# MCU.net
KiCad netlist of a schematic drawn in Altium Designer
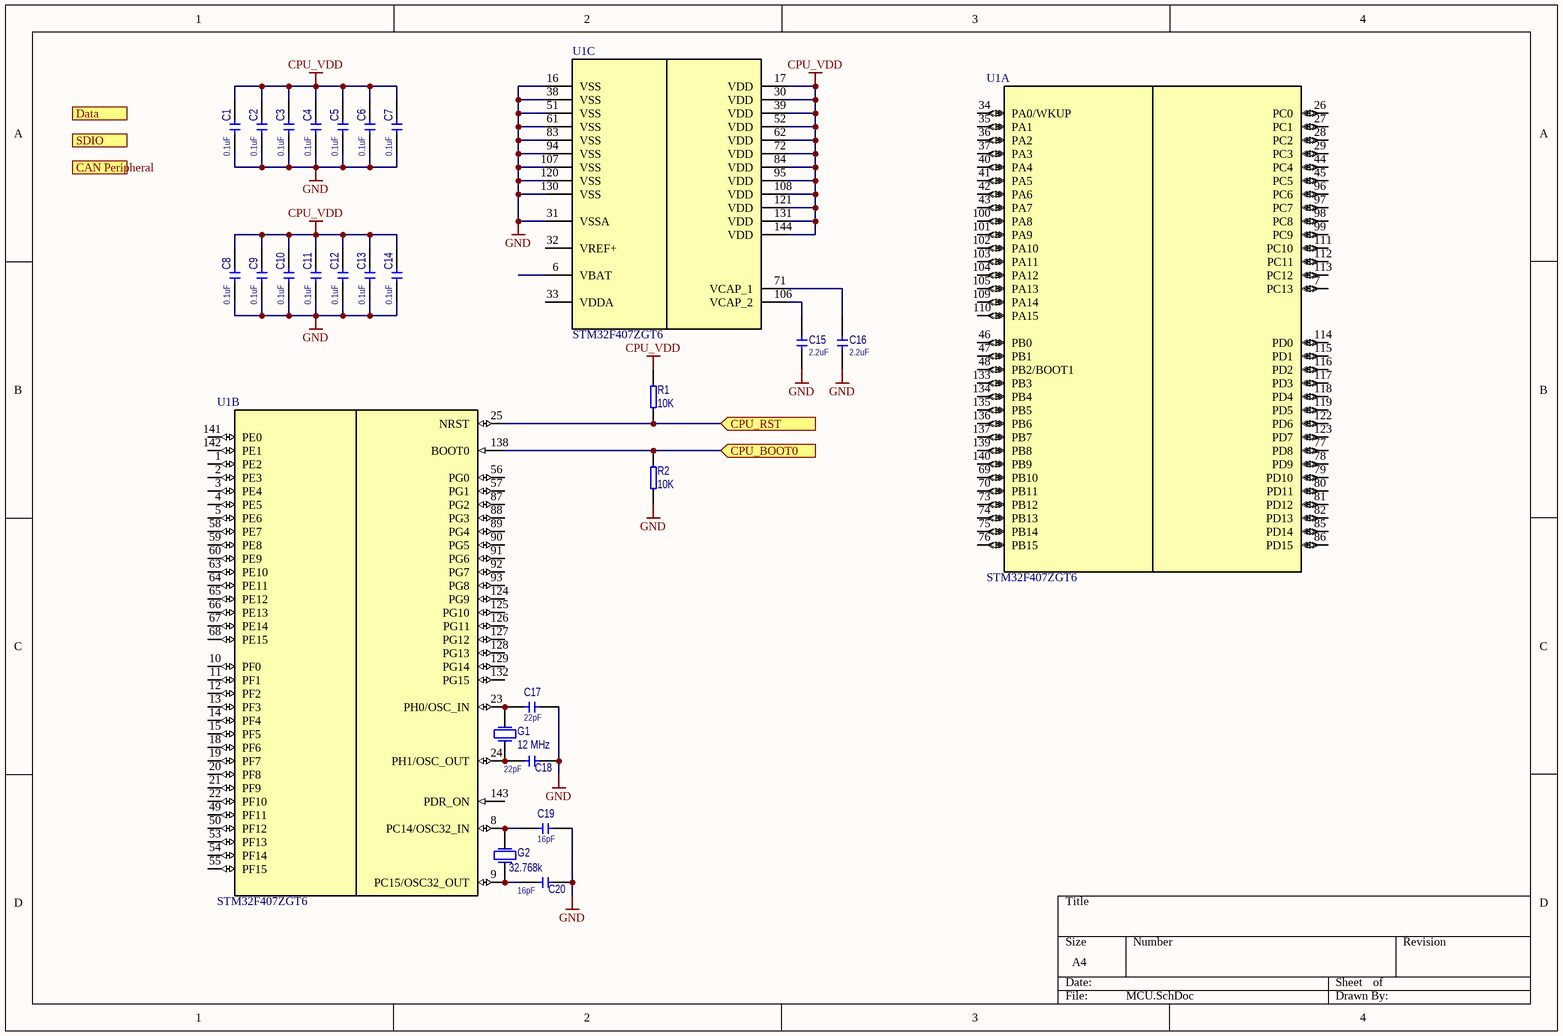
[diagram p0: MCU.SchDoc]

(export (version "E")
  (design (tool "Eeschema 10.0.6"))
  (components
    (comp (ref "C1")
      (value "0.1uF")
      (footprint "CERCAP 0603")
      (description "Capacitor")
      (fields (field (name "Comment") "CERCAP 0603 0.1uF * X7R"))
      (libsource (lib "!main") (part "!Capacitor"))
    )
    (comp (ref "C2")
      (value "0.1uF")
      (footprint "CERCAP 0603")
      (description "Capacitor")
      (fields (field (name "Comment") "CERCAP 0603 0.1uF * X7R"))
      (libsource (lib "!main") (part "!Capacitor"))
    )
    (comp (ref "C3")
      (value "0.1uF")
      (footprint "CERCAP 0603")
      (description "Capacitor")
      (fields (field (name "Comment") "CERCAP 0603 0.1uF * X7R"))
      (libsource (lib "!main") (part "!Capacitor"))
    )
    (comp (ref "C4")
      (value "0.1uF")
      (footprint "CERCAP 0603")
      (description "Capacitor")
      (fields (field (name "Comment") "CERCAP 0603 0.1uF * X7R"))
      (libsource (lib "!main") (part "!Capacitor"))
    )
    (comp (ref "C5")
      (value "0.1uF")
      (footprint "CERCAP 0603")
      (description "Capacitor")
      (fields (field (name "Comment") "CERCAP 0603 0.1uF * X7R"))
      (libsource (lib "!main") (part "!Capacitor"))
    )
    (comp (ref "C6")
      (value "0.1uF")
      (footprint "CERCAP 0603")
      (description "Capacitor")
      (fields (field (name "Comment") "CERCAP 0603 0.1uF * X7R"))
      (libsource (lib "!main") (part "!Capacitor"))
    )
    (comp (ref "C7")
      (value "0.1uF")
      (footprint "CERCAP 0603")
      (description "Capacitor")
      (fields (field (name "Comment") "CERCAP 0603 0.1uF * X7R"))
      (libsource (lib "!main") (part "!Capacitor"))
    )
    (comp (ref "C8")
      (value "0.1uF")
      (footprint "CERCAP 0603")
      (description "Capacitor")
      (fields (field (name "Comment") "CERCAP 0603 0.1uF * X7R"))
      (libsource (lib "!main") (part "!Capacitor"))
    )
    (comp (ref "C9")
      (value "0.1uF")
      (footprint "CERCAP 0603")
      (description "Capacitor")
      (fields (field (name "Comment") "CERCAP 0603 0.1uF * X7R"))
      (libsource (lib "!main") (part "!Capacitor"))
    )
    (comp (ref "C10")
      (value "0.1uF")
      (footprint "CERCAP 0603")
      (description "Capacitor")
      (fields (field (name "Comment") "CERCAP 0603 0.1uF * X7R"))
      (libsource (lib "!main") (part "!Capacitor"))
    )
    (comp (ref "C11")
      (value "0.1uF")
      (footprint "CERCAP 0603")
      (description "Capacitor")
      (fields (field (name "Comment") "CERCAP 0603 0.1uF * X7R"))
      (libsource (lib "!main") (part "!Capacitor"))
    )
    (comp (ref "C12")
      (value "0.1uF")
      (footprint "CERCAP 0603")
      (description "Capacitor")
      (fields (field (name "Comment") "CERCAP 0603 0.1uF * X7R"))
      (libsource (lib "!main") (part "!Capacitor"))
    )
    (comp (ref "C13")
      (value "0.1uF")
      (footprint "CERCAP 0603")
      (description "Capacitor")
      (fields (field (name "Comment") "CERCAP 0603 0.1uF * X7R"))
      (libsource (lib "!main") (part "!Capacitor"))
    )
    (comp (ref "C14")
      (value "0.1uF")
      (footprint "CERCAP 0603")
      (description "Capacitor")
      (fields (field (name "Comment") "CERCAP 0603 0.1uF * X7R"))
      (libsource (lib "!main") (part "!Capacitor"))
    )
    (comp (ref "C15")
      (value "2.2uF")
      (footprint "CERCAP 0603")
      (description "Capacitor")
      (fields (field (name "Comment") "CERCAP 0603 2.2uF * X7R"))
      (libsource (lib "!main") (part "!Capacitor"))
    )
    (comp (ref "C16")
      (value "2.2uF")
      (footprint "CERCAP 0603")
      (description "Capacitor")
      (fields (field (name "Comment") "CERCAP 0603 2.2uF * X7R"))
      (libsource (lib "!main") (part "!Capacitor"))
    )
    (comp (ref "C17")
      (value "22pF")
      (footprint "CERCAP 0402")
      (description "Capacitor")
      (fields (field (name "Comment") "CERCAP 0402 22pF * X7R"))
      (libsource (lib "!main") (part "!Capacitor"))
    )
    (comp (ref "C18")
      (value "22pF")
      (footprint "CERCAP 0402")
      (description "Capacitor")
      (fields (field (name "Comment") "CERCAP 0402 22pF * X7R"))
      (libsource (lib "!main") (part "!Capacitor"))
    )
    (comp (ref "C19")
      (value "16pF")
      (footprint "CERCAP 0402")
      (description "Capacitor")
      (fields (field (name "Comment") "CERCAP 0402 16pF * X7R"))
      (libsource (lib "!main") (part "!Capacitor"))
    )
    (comp (ref "C20")
      (value "16pF")
      (footprint "CERCAP 0402")
      (description "Capacitor")
      (fields (field (name "Comment") "CERCAP 0402 16pF * X7R"))
      (libsource (lib "!main") (part "!Capacitor"))
    )
    (comp (ref "G1")
      (value "12 MHz")
      (footprint "3225")
      (description "Crystal")
      (fields (field (name "Comment") "322512 MHz"))
      (libsource (lib "!main") (part "Crystal"))
    )
    (comp (ref "G2")
      (value "32.768k")
      (footprint "1210")
      (description "Crystal")
      (fields (field (name "Comment") "121032.768k"))
      (libsource (lib "!main") (part "Crystal"))
    )
    (comp (ref "R1")
      (value "10K")
      (footprint "RES 0402")
      (description "Resistor")
      (fields (field (name "Comment") "RES 0402 10K"))
      (libsource (lib "!main") (part "!Resistor"))
    )
    (comp (ref "R2")
      (value "10K")
      (footprint "RES 0402")
      (description "Resistor")
      (fields (field (name "Comment") "RES 0402 10K"))
      (libsource (lib "!main") (part "!Resistor"))
    )
    (comp (ref "U1")
      (value "STM32F407ZGT6")
      (footprint "LQFP-144")
      (description "Coretx-M4")
      (libsource (lib "MCU_CPU") (part "STM32F407ZGT6"))
    )
  )
  (nets
    (net (code "2") (name "/CPU_BOOT0") (class "Default")
      (node (ref "R2") (pin "2") (pinfunction "12_2") (pintype "passive"))
      (node (ref "U1") (pin "138") (pinfunction "BOOT0_138") (pintype "input"))
    )
    (net (code "3") (name "/CPU_RST") (class "Default")
      (node (ref "R1") (pin "2") (pinfunction "12_2") (pintype "passive"))
      (node (ref "U1") (pin "25") (pinfunction "NRST_25") (pintype "bidirectional"))
    )
    (net (code "6") (name "CPU_VDD") (class "Default")
      (node (ref "C1") (pin "1") (pintype "passive"))
      (node (ref "C10") (pin "1") (pintype "passive"))
      (node (ref "C11") (pin "1") (pintype "passive"))
      (node (ref "C12") (pin "1") (pintype "passive"))
      (node (ref "C13") (pin "1") (pintype "passive"))
      (node (ref "C14") (pin "1") (pintype "passive"))
      (node (ref "C2") (pin "1") (pintype "passive"))
      (node (ref "C3") (pin "1") (pintype "passive"))
      (node (ref "C4") (pin "1") (pintype "passive"))
      (node (ref "C5") (pin "1") (pintype "passive"))
      (node (ref "C6") (pin "1") (pintype "passive"))
      (node (ref "C7") (pin "1") (pintype "passive"))
      (node (ref "C8") (pin "1") (pintype "passive"))
      (node (ref "C9") (pin "1") (pintype "passive"))
      (node (ref "R1") (pin "1") (pinfunction "11_1") (pintype "passive"))
      (node (ref "U1") (pin "108") (pinfunction "VDD_108") (pintype "power_in"))
      (node (ref "U1") (pin "121") (pinfunction "VDD_121") (pintype "power_in"))
      (node (ref "U1") (pin "131") (pinfunction "VDD_131") (pintype "power_in"))
      (node (ref "U1") (pin "144") (pinfunction "VDD_144") (pintype "power_in"))
      (node (ref "U1") (pin "17") (pinfunction "VDD_17") (pintype "power_in"))
      (node (ref "U1") (pin "30") (pinfunction "VDD_30") (pintype "power_in"))
      (node (ref "U1") (pin "39") (pinfunction "VDD_39") (pintype "power_in"))
      (node (ref "U1") (pin "52") (pinfunction "VDD_52") (pintype "power_in"))
      (node (ref "U1") (pin "62") (pinfunction "VDD_62") (pintype "power_in"))
      (node (ref "U1") (pin "72") (pinfunction "VDD_72") (pintype "power_in"))
      (node (ref "U1") (pin "84") (pinfunction "VDD_84") (pintype "power_in"))
      (node (ref "U1") (pin "95") (pinfunction "VDD_95") (pintype "power_in"))
    )
    (net (code "7") (name "GND") (class "Default")
      (node (ref "C1") (pin "2") (pintype "passive"))
      (node (ref "C10") (pin "2") (pintype "passive"))
      (node (ref "C11") (pin "2") (pintype "passive"))
      (node (ref "C12") (pin "2") (pintype "passive"))
      (node (ref "C13") (pin "2") (pintype "passive"))
      (node (ref "C14") (pin "2") (pintype "passive"))
      (node (ref "C15") (pin "2") (pintype "passive"))
      (node (ref "C16") (pin "2") (pintype "passive"))
      (node (ref "C17") (pin "2") (pintype "passive"))
      (node (ref "C18") (pin "2") (pintype "passive"))
      (node (ref "C19") (pin "2") (pintype "passive"))
      (node (ref "C2") (pin "2") (pintype "passive"))
      (node (ref "C20") (pin "2") (pintype "passive"))
      (node (ref "C3") (pin "2") (pintype "passive"))
      (node (ref "C4") (pin "2") (pintype "passive"))
      (node (ref "C5") (pin "2") (pintype "passive"))
      (node (ref "C6") (pin "2") (pintype "passive"))
      (node (ref "C7") (pin "2") (pintype "passive"))
      (node (ref "C8") (pin "2") (pintype "passive"))
      (node (ref "C9") (pin "2") (pintype "passive"))
      (node (ref "R2") (pin "1") (pinfunction "11_1") (pintype "passive"))
      (node (ref "U1") (pin "107") (pinfunction "VSS_107") (pintype "power_in"))
      (node (ref "U1") (pin "120") (pinfunction "VSS_120") (pintype "power_in"))
      (node (ref "U1") (pin "130") (pinfunction "VSS_130") (pintype "power_in"))
      (node (ref "U1") (pin "16") (pinfunction "VSS_16") (pintype "power_in"))
      (node (ref "U1") (pin "31") (pinfunction "VSSA_31") (pintype "power_in"))
      (node (ref "U1") (pin "38") (pinfunction "VSS_38") (pintype "power_in"))
      (node (ref "U1") (pin "51") (pinfunction "VSS_51") (pintype "power_in"))
      (node (ref "U1") (pin "61") (pinfunction "VSS_61") (pintype "power_in"))
      (node (ref "U1") (pin "83") (pinfunction "VSS_83") (pintype "power_in"))
      (node (ref "U1") (pin "94") (pinfunction "VSS_94") (pintype "power_in"))
    )
    (net (code "8") (name "Net-(U1B-PC14{slash}OSC32_IN)") (class "Default")
      (node (ref "C19") (pin "1") (pintype "passive"))
      (node (ref "G2") (pin "1") (pintype "passive"))
      (node (ref "U1") (pin "8") (pinfunction "PC14/OSC32_IN_8") (pintype "bidirectional"))
    )
    (net (code "9") (name "Net-(U1B-PC15{slash}OSC32_OUT)") (class "Default")
      (node (ref "C20") (pin "1") (pintype "passive"))
      (node (ref "G2") (pin "2") (pintype "passive"))
      (node (ref "U1") (pin "9") (pinfunction "PC15/OSC32_OUT_9") (pintype "bidirectional"))
    )
    (net (code "10") (name "Net-(U1B-PH0{slash}OSC_IN)") (class "Default")
      (node (ref "C17") (pin "1") (pintype "passive"))
      (node (ref "G1") (pin "1") (pintype "passive"))
      (node (ref "U1") (pin "23") (pinfunction "PH0/OSC_IN_23") (pintype "bidirectional"))
    )
    (net (code "11") (name "Net-(U1B-PH1{slash}OSC_OUT)") (class "Default")
      (node (ref "C18") (pin "1") (pintype "passive"))
      (node (ref "G1") (pin "2") (pintype "passive"))
      (node (ref "U1") (pin "24") (pinfunction "PH1/OSC_OUT_24") (pintype "bidirectional"))
    )
    (net (code "12") (name "Net-(U1C-VCAP_1)") (class "Default")
      (node (ref "C16") (pin "1") (pintype "passive"))
      (node (ref "U1") (pin "71") (pinfunction "VCAP_1_71") (pintype "power_in"))
    )
    (net (code "13") (name "Net-(U1C-VCAP_2)") (class "Default")
      (node (ref "C15") (pin "1") (pintype "passive"))
      (node (ref "U1") (pin "106") (pinfunction "VCAP_2_106") (pintype "power_in"))
    )
    (net (code "14") (name "unconnected-(U1A-PA0{slash}WKUP-Pad34)") (class "Default")
      (node (ref "U1") (pin "34") (pinfunction "PA0/WKUP_34") (pintype "bidirectional"))
    )
    (net (code "15") (name "unconnected-(U1A-PA1-Pad35)") (class "Default")
      (node (ref "U1") (pin "35") (pinfunction "PA1_35") (pintype "bidirectional"))
    )
    (net (code "16") (name "unconnected-(U1A-PA2-Pad36)") (class "Default")
      (node (ref "U1") (pin "36") (pinfunction "PA2_36") (pintype "bidirectional"))
    )
    (net (code "17") (name "unconnected-(U1A-PA3-Pad37)") (class "Default")
      (node (ref "U1") (pin "37") (pinfunction "PA3_37") (pintype "bidirectional"))
    )
    (net (code "18") (name "unconnected-(U1A-PA4-Pad40)") (class "Default")
      (node (ref "U1") (pin "40") (pinfunction "PA4_40") (pintype "bidirectional"))
    )
    (net (code "19") (name "unconnected-(U1A-PA5-Pad41)") (class "Default")
      (node (ref "U1") (pin "41") (pinfunction "PA5_41") (pintype "bidirectional"))
    )
    (net (code "20") (name "unconnected-(U1A-PA6-Pad42)") (class "Default")
      (node (ref "U1") (pin "42") (pinfunction "PA6_42") (pintype "bidirectional"))
    )
    (net (code "21") (name "unconnected-(U1A-PA7-Pad43)") (class "Default")
      (node (ref "U1") (pin "43") (pinfunction "PA7_43") (pintype "bidirectional"))
    )
    (net (code "22") (name "unconnected-(U1A-PA8-Pad100)") (class "Default")
      (node (ref "U1") (pin "100") (pinfunction "PA8_100") (pintype "bidirectional"))
    )
    (net (code "23") (name "unconnected-(U1A-PA9-Pad101)") (class "Default")
      (node (ref "U1") (pin "101") (pinfunction "PA9_101") (pintype "bidirectional"))
    )
    (net (code "24") (name "unconnected-(U1A-PA10-Pad102)") (class "Default")
      (node (ref "U1") (pin "102") (pinfunction "PA10_102") (pintype "bidirectional"))
    )
    (net (code "25") (name "unconnected-(U1A-PA11-Pad103)") (class "Default")
      (node (ref "U1") (pin "103") (pinfunction "PA11_103") (pintype "bidirectional"))
    )
    (net (code "26") (name "unconnected-(U1A-PA12-Pad104)") (class "Default")
      (node (ref "U1") (pin "104") (pinfunction "PA12_104") (pintype "bidirectional"))
    )
    (net (code "27") (name "unconnected-(U1A-PA13-Pad105)") (class "Default")
      (node (ref "U1") (pin "105") (pinfunction "PA13_105") (pintype "bidirectional"))
    )
    (net (code "28") (name "unconnected-(U1A-PA14-Pad109)") (class "Default")
      (node (ref "U1") (pin "109") (pinfunction "PA14_109") (pintype "bidirectional"))
    )
    (net (code "29") (name "unconnected-(U1A-PA15-Pad110)") (class "Default")
      (node (ref "U1") (pin "110") (pinfunction "PA15_110") (pintype "bidirectional"))
    )
    (net (code "30") (name "unconnected-(U1A-PB0-Pad46)") (class "Default")
      (node (ref "U1") (pin "46") (pinfunction "PB0_46") (pintype "bidirectional"))
    )
    (net (code "31") (name "unconnected-(U1A-PB1-Pad47)") (class "Default")
      (node (ref "U1") (pin "47") (pinfunction "PB1_47") (pintype "bidirectional"))
    )
    (net (code "32") (name "unconnected-(U1A-PB2{slash}BOOT1-Pad48)") (class "Default")
      (node (ref "U1") (pin "48") (pinfunction "PB2/BOOT1_48") (pintype "bidirectional"))
    )
    (net (code "33") (name "unconnected-(U1A-PB3-Pad133)") (class "Default")
      (node (ref "U1") (pin "133") (pinfunction "PB3_133") (pintype "bidirectional"))
    )
    (net (code "34") (name "unconnected-(U1A-PB4-Pad134)") (class "Default")
      (node (ref "U1") (pin "134") (pinfunction "PB4_134") (pintype "bidirectional"))
    )
    (net (code "35") (name "unconnected-(U1A-PB5-Pad135)") (class "Default")
      (node (ref "U1") (pin "135") (pinfunction "PB5_135") (pintype "bidirectional"))
    )
    (net (code "36") (name "unconnected-(U1A-PB6-Pad136)") (class "Default")
      (node (ref "U1") (pin "136") (pinfunction "PB6_136") (pintype "bidirectional"))
    )
    (net (code "37") (name "unconnected-(U1A-PB7-Pad137)") (class "Default")
      (node (ref "U1") (pin "137") (pinfunction "PB7_137") (pintype "bidirectional"))
    )
    (net (code "38") (name "unconnected-(U1A-PB8-Pad139)") (class "Default")
      (node (ref "U1") (pin "139") (pinfunction "PB8_139") (pintype "bidirectional"))
    )
    (net (code "39") (name "unconnected-(U1A-PB9-Pad140)") (class "Default")
      (node (ref "U1") (pin "140") (pinfunction "PB9_140") (pintype "bidirectional"))
    )
    (net (code "40") (name "unconnected-(U1A-PB10-Pad69)") (class "Default")
      (node (ref "U1") (pin "69") (pinfunction "PB10_69") (pintype "bidirectional"))
    )
    (net (code "41") (name "unconnected-(U1A-PB11-Pad70)") (class "Default")
      (node (ref "U1") (pin "70") (pinfunction "PB11_70") (pintype "bidirectional"))
    )
    (net (code "42") (name "unconnected-(U1A-PB12-Pad73)") (class "Default")
      (node (ref "U1") (pin "73") (pinfunction "PB12_73") (pintype "bidirectional"))
    )
    (net (code "43") (name "unconnected-(U1A-PB13-Pad74)") (class "Default")
      (node (ref "U1") (pin "74") (pinfunction "PB13_74") (pintype "bidirectional"))
    )
    (net (code "44") (name "unconnected-(U1A-PB14-Pad75)") (class "Default")
      (node (ref "U1") (pin "75") (pinfunction "PB14_75") (pintype "bidirectional"))
    )
    (net (code "45") (name "unconnected-(U1A-PB15-Pad76)") (class "Default")
      (node (ref "U1") (pin "76") (pinfunction "PB15_76") (pintype "bidirectional"))
    )
    (net (code "46") (name "unconnected-(U1A-PC0-Pad26)") (class "Default")
      (node (ref "U1") (pin "26") (pinfunction "PC0_26") (pintype "bidirectional"))
    )
    (net (code "47") (name "unconnected-(U1A-PC1-Pad27)") (class "Default")
      (node (ref "U1") (pin "27") (pinfunction "PC1_27") (pintype "bidirectional"))
    )
    (net (code "48") (name "unconnected-(U1A-PC2-Pad28)") (class "Default")
      (node (ref "U1") (pin "28") (pinfunction "PC2_28") (pintype "bidirectional"))
    )
    (net (code "49") (name "unconnected-(U1A-PC3-Pad29)") (class "Default")
      (node (ref "U1") (pin "29") (pinfunction "PC3_29") (pintype "bidirectional"))
    )
    (net (code "50") (name "unconnected-(U1A-PC4-Pad44)") (class "Default")
      (node (ref "U1") (pin "44") (pinfunction "PC4_44") (pintype "bidirectional"))
    )
    (net (code "51") (name "unconnected-(U1A-PC5-Pad45)") (class "Default")
      (node (ref "U1") (pin "45") (pinfunction "PC5_45") (pintype "bidirectional"))
    )
    (net (code "52") (name "unconnected-(U1A-PC6-Pad96)") (class "Default")
      (node (ref "U1") (pin "96") (pinfunction "PC6_96") (pintype "bidirectional"))
    )
    (net (code "53") (name "unconnected-(U1A-PC7-Pad97)") (class "Default")
      (node (ref "U1") (pin "97") (pinfunction "PC7_97") (pintype "bidirectional"))
    )
    (net (code "54") (name "unconnected-(U1A-PC8-Pad98)") (class "Default")
      (node (ref "U1") (pin "98") (pinfunction "PC8_98") (pintype "bidirectional"))
    )
    (net (code "55") (name "unconnected-(U1A-PC9-Pad99)") (class "Default")
      (node (ref "U1") (pin "99") (pinfunction "PC9_99") (pintype "bidirectional"))
    )
    (net (code "56") (name "unconnected-(U1A-PC10-Pad111)") (class "Default")
      (node (ref "U1") (pin "111") (pinfunction "PC10_111") (pintype "bidirectional"))
    )
    (net (code "57") (name "unconnected-(U1A-PC11-Pad112)") (class "Default")
      (node (ref "U1") (pin "112") (pinfunction "PC11_112") (pintype "bidirectional"))
    )
    (net (code "58") (name "unconnected-(U1A-PC12-Pad113)") (class "Default")
      (node (ref "U1") (pin "113") (pinfunction "PC12_113") (pintype "bidirectional"))
    )
    (net (code "59") (name "unconnected-(U1A-PC13-Pad7)") (class "Default")
      (node (ref "U1") (pin "7") (pinfunction "PC13_7") (pintype "bidirectional"))
    )
    (net (code "60") (name "unconnected-(U1A-PD0-Pad114)") (class "Default")
      (node (ref "U1") (pin "114") (pinfunction "PD0_114") (pintype "bidirectional"))
    )
    (net (code "61") (name "unconnected-(U1A-PD1-Pad115)") (class "Default")
      (node (ref "U1") (pin "115") (pinfunction "PD1_115") (pintype "bidirectional"))
    )
    (net (code "62") (name "unconnected-(U1A-PD2-Pad116)") (class "Default")
      (node (ref "U1") (pin "116") (pinfunction "PD2_116") (pintype "bidirectional"))
    )
    (net (code "63") (name "unconnected-(U1A-PD3-Pad117)") (class "Default")
      (node (ref "U1") (pin "117") (pinfunction "PD3_117") (pintype "bidirectional"))
    )
    (net (code "64") (name "unconnected-(U1A-PD4-Pad118)") (class "Default")
      (node (ref "U1") (pin "118") (pinfunction "PD4_118") (pintype "bidirectional"))
    )
    (net (code "65") (name "unconnected-(U1A-PD5-Pad119)") (class "Default")
      (node (ref "U1") (pin "119") (pinfunction "PD5_119") (pintype "bidirectional"))
    )
    (net (code "66") (name "unconnected-(U1A-PD6-Pad122)") (class "Default")
      (node (ref "U1") (pin "122") (pinfunction "PD6_122") (pintype "bidirectional"))
    )
    (net (code "67") (name "unconnected-(U1A-PD7-Pad123)") (class "Default")
      (node (ref "U1") (pin "123") (pinfunction "PD7_123") (pintype "bidirectional"))
    )
    (net (code "68") (name "unconnected-(U1A-PD8-Pad77)") (class "Default")
      (node (ref "U1") (pin "77") (pinfunction "PD8_77") (pintype "bidirectional"))
    )
    (net (code "69") (name "unconnected-(U1A-PD9-Pad78)") (class "Default")
      (node (ref "U1") (pin "78") (pinfunction "PD9_78") (pintype "bidirectional"))
    )
    (net (code "70") (name "unconnected-(U1A-PD10-Pad79)") (class "Default")
      (node (ref "U1") (pin "79") (pinfunction "PD10_79") (pintype "bidirectional"))
    )
    (net (code "71") (name "unconnected-(U1A-PD11-Pad80)") (class "Default")
      (node (ref "U1") (pin "80") (pinfunction "PD11_80") (pintype "bidirectional"))
    )
    (net (code "72") (name "unconnected-(U1A-PD12-Pad81)") (class "Default")
      (node (ref "U1") (pin "81") (pinfunction "PD12_81") (pintype "bidirectional"))
    )
    (net (code "73") (name "unconnected-(U1A-PD13-Pad82)") (class "Default")
      (node (ref "U1") (pin "82") (pinfunction "PD13_82") (pintype "bidirectional"))
    )
    (net (code "74") (name "unconnected-(U1A-PD14-Pad85)") (class "Default")
      (node (ref "U1") (pin "85") (pinfunction "PD14_85") (pintype "bidirectional"))
    )
    (net (code "75") (name "unconnected-(U1A-PD15-Pad86)") (class "Default")
      (node (ref "U1") (pin "86") (pinfunction "PD15_86") (pintype "bidirectional"))
    )
    (net (code "76") (name "unconnected-(U1B-PDR_ON-Pad143)") (class "Default")
      (node (ref "U1") (pin "143") (pinfunction "PDR_ON_143") (pintype "input"))
    )
    (net (code "77") (name "unconnected-(U1B-PE0-Pad141)") (class "Default")
      (node (ref "U1") (pin "141") (pinfunction "PE0_141") (pintype "bidirectional"))
    )
    (net (code "78") (name "unconnected-(U1B-PE1-Pad142)") (class "Default")
      (node (ref "U1") (pin "142") (pinfunction "PE1_142") (pintype "bidirectional"))
    )
    (net (code "79") (name "unconnected-(U1B-PE2-Pad1)") (class "Default")
      (node (ref "U1") (pin "1") (pinfunction "PE2_1") (pintype "bidirectional"))
    )
    (net (code "80") (name "unconnected-(U1B-PE3-Pad2)") (class "Default")
      (node (ref "U1") (pin "2") (pinfunction "PE3_2") (pintype "bidirectional"))
    )
    (net (code "81") (name "unconnected-(U1B-PE4-Pad3)") (class "Default")
      (node (ref "U1") (pin "3") (pinfunction "PE4_3") (pintype "bidirectional"))
    )
    (net (code "82") (name "unconnected-(U1B-PE5-Pad4)") (class "Default")
      (node (ref "U1") (pin "4") (pinfunction "PE5_4") (pintype "bidirectional"))
    )
    (net (code "83") (name "unconnected-(U1B-PE6-Pad5)") (class "Default")
      (node (ref "U1") (pin "5") (pinfunction "PE6_5") (pintype "bidirectional"))
    )
    (net (code "84") (name "unconnected-(U1B-PE7-Pad58)") (class "Default")
      (node (ref "U1") (pin "58") (pinfunction "PE7_58") (pintype "bidirectional"))
    )
    (net (code "85") (name "unconnected-(U1B-PE8-Pad59)") (class "Default")
      (node (ref "U1") (pin "59") (pinfunction "PE8_59") (pintype "bidirectional"))
    )
    (net (code "86") (name "unconnected-(U1B-PE9-Pad60)") (class "Default")
      (node (ref "U1") (pin "60") (pinfunction "PE9_60") (pintype "bidirectional"))
    )
    (net (code "87") (name "unconnected-(U1B-PE10-Pad63)") (class "Default")
      (node (ref "U1") (pin "63") (pinfunction "PE10_63") (pintype "bidirectional"))
    )
    (net (code "88") (name "unconnected-(U1B-PE11-Pad64)") (class "Default")
      (node (ref "U1") (pin "64") (pinfunction "PE11_64") (pintype "bidirectional"))
    )
    (net (code "89") (name "unconnected-(U1B-PE12-Pad65)") (class "Default")
      (node (ref "U1") (pin "65") (pinfunction "PE12_65") (pintype "bidirectional"))
    )
    (net (code "90") (name "unconnected-(U1B-PE13-Pad66)") (class "Default")
      (node (ref "U1") (pin "66") (pinfunction "PE13_66") (pintype "bidirectional"))
    )
    (net (code "91") (name "unconnected-(U1B-PE14-Pad67)") (class "Default")
      (node (ref "U1") (pin "67") (pinfunction "PE14_67") (pintype "bidirectional"))
    )
    (net (code "92") (name "unconnected-(U1B-PE15-Pad68)") (class "Default")
      (node (ref "U1") (pin "68") (pinfunction "PE15_68") (pintype "bidirectional"))
    )
    (net (code "93") (name "unconnected-(U1B-PF0-Pad10)") (class "Default")
      (node (ref "U1") (pin "10") (pinfunction "PF0_10") (pintype "bidirectional"))
    )
    (net (code "94") (name "unconnected-(U1B-PF1-Pad11)") (class "Default")
      (node (ref "U1") (pin "11") (pinfunction "PF1_11") (pintype "bidirectional"))
    )
    (net (code "95") (name "unconnected-(U1B-PF2-Pad12)") (class "Default")
      (node (ref "U1") (pin "12") (pinfunction "PF2_12") (pintype "bidirectional"))
    )
    (net (code "96") (name "unconnected-(U1B-PF3-Pad13)") (class "Default")
      (node (ref "U1") (pin "13") (pinfunction "PF3_13") (pintype "bidirectional"))
    )
    (net (code "97") (name "unconnected-(U1B-PF4-Pad14)") (class "Default")
      (node (ref "U1") (pin "14") (pinfunction "PF4_14") (pintype "bidirectional"))
    )
    (net (code "98") (name "unconnected-(U1B-PF5-Pad15)") (class "Default")
      (node (ref "U1") (pin "15") (pinfunction "PF5_15") (pintype "bidirectional"))
    )
    (net (code "99") (name "unconnected-(U1B-PF6-Pad18)") (class "Default")
      (node (ref "U1") (pin "18") (pinfunction "PF6_18") (pintype "bidirectional"))
    )
    (net (code "100") (name "unconnected-(U1B-PF7-Pad19)") (class "Default")
      (node (ref "U1") (pin "19") (pinfunction "PF7_19") (pintype "bidirectional"))
    )
    (net (code "101") (name "unconnected-(U1B-PF8-Pad20)") (class "Default")
      (node (ref "U1") (pin "20") (pinfunction "PF8_20") (pintype "bidirectional"))
    )
    (net (code "102") (name "unconnected-(U1B-PF9-Pad21)") (class "Default")
      (node (ref "U1") (pin "21") (pinfunction "PF9_21") (pintype "bidirectional"))
    )
    (net (code "103") (name "unconnected-(U1B-PF10-Pad22)") (class "Default")
      (node (ref "U1") (pin "22") (pinfunction "PF10_22") (pintype "bidirectional"))
    )
    (net (code "104") (name "unconnected-(U1B-PF11-Pad49)") (class "Default")
      (node (ref "U1") (pin "49") (pinfunction "PF11_49") (pintype "bidirectional"))
    )
    (net (code "105") (name "unconnected-(U1B-PF12-Pad50)") (class "Default")
      (node (ref "U1") (pin "50") (pinfunction "PF12_50") (pintype "bidirectional"))
    )
    (net (code "106") (name "unconnected-(U1B-PF13-Pad53)") (class "Default")
      (node (ref "U1") (pin "53") (pinfunction "PF13_53") (pintype "bidirectional"))
    )
    (net (code "107") (name "unconnected-(U1B-PF14-Pad54)") (class "Default")
      (node (ref "U1") (pin "54") (pinfunction "PF14_54") (pintype "bidirectional"))
    )
    (net (code "108") (name "unconnected-(U1B-PF15-Pad55)") (class "Default")
      (node (ref "U1") (pin "55") (pinfunction "PF15_55") (pintype "bidirectional"))
    )
    (net (code "109") (name "unconnected-(U1B-PG0-Pad56)") (class "Default")
      (node (ref "U1") (pin "56") (pinfunction "PG0_56") (pintype "bidirectional"))
    )
    (net (code "110") (name "unconnected-(U1B-PG1-Pad57)") (class "Default")
      (node (ref "U1") (pin "57") (pinfunction "PG1_57") (pintype "bidirectional"))
    )
    (net (code "111") (name "unconnected-(U1B-PG2-Pad87)") (class "Default")
      (node (ref "U1") (pin "87") (pinfunction "PG2_87") (pintype "bidirectional"))
    )
    (net (code "112") (name "unconnected-(U1B-PG3-Pad88)") (class "Default")
      (node (ref "U1") (pin "88") (pinfunction "PG3_88") (pintype "bidirectional"))
    )
    (net (code "113") (name "unconnected-(U1B-PG4-Pad89)") (class "Default")
      (node (ref "U1") (pin "89") (pinfunction "PG4_89") (pintype "bidirectional"))
    )
    (net (code "114") (name "unconnected-(U1B-PG5-Pad90)") (class "Default")
      (node (ref "U1") (pin "90") (pinfunction "PG5_90") (pintype "bidirectional"))
    )
    (net (code "115") (name "unconnected-(U1B-PG6-Pad91)") (class "Default")
      (node (ref "U1") (pin "91") (pinfunction "PG6_91") (pintype "bidirectional"))
    )
    (net (code "116") (name "unconnected-(U1B-PG7-Pad92)") (class "Default")
      (node (ref "U1") (pin "92") (pinfunction "PG7_92") (pintype "bidirectional"))
    )
    (net (code "117") (name "unconnected-(U1B-PG8-Pad93)") (class "Default")
      (node (ref "U1") (pin "93") (pinfunction "PG8_93") (pintype "bidirectional"))
    )
    (net (code "118") (name "unconnected-(U1B-PG9-Pad124)") (class "Default")
      (node (ref "U1") (pin "124") (pinfunction "PG9_124") (pintype "bidirectional"))
    )
    (net (code "119") (name "unconnected-(U1B-PG10-Pad125)") (class "Default")
      (node (ref "U1") (pin "125") (pinfunction "PG10_125") (pintype "bidirectional"))
    )
    (net (code "120") (name "unconnected-(U1B-PG11-Pad126)") (class "Default")
      (node (ref "U1") (pin "126") (pinfunction "PG11_126") (pintype "bidirectional"))
    )
    (net (code "121") (name "unconnected-(U1B-PG12-Pad127)") (class "Default")
      (node (ref "U1") (pin "127") (pinfunction "PG12_127") (pintype "bidirectional"))
    )
    (net (code "122") (name "unconnected-(U1B-PG13-Pad128)") (class "Default")
      (node (ref "U1") (pin "128") (pinfunction "PG13_128") (pintype "bidirectional"))
    )
    (net (code "123") (name "unconnected-(U1B-PG14-Pad129)") (class "Default")
      (node (ref "U1") (pin "129") (pinfunction "PG14_129") (pintype "bidirectional"))
    )
    (net (code "124") (name "unconnected-(U1B-PG15-Pad132)") (class "Default")
      (node (ref "U1") (pin "132") (pinfunction "PG15_132") (pintype "bidirectional"))
    )
    (net (code "125") (name "unconnected-(U1C-VBAT-Pad6)") (class "Default")
      (node (ref "U1") (pin "6") (pinfunction "VBAT_6") (pintype "power_in"))
    )
    (net (code "126") (name "unconnected-(U1C-VDDA-Pad33)") (class "Default")
      (node (ref "U1") (pin "33") (pinfunction "VDDA_33") (pintype "power_in"))
    )
    (net (code "127") (name "unconnected-(U1C-VREF+-Pad32)") (class "Default")
      (node (ref "U1") (pin "32") (pinfunction "VREF+_32") (pintype "power_in"))
    )
  )
)
